# FunctionGenerator.net
KiCad netlist of a schematic drawn in EAGLE
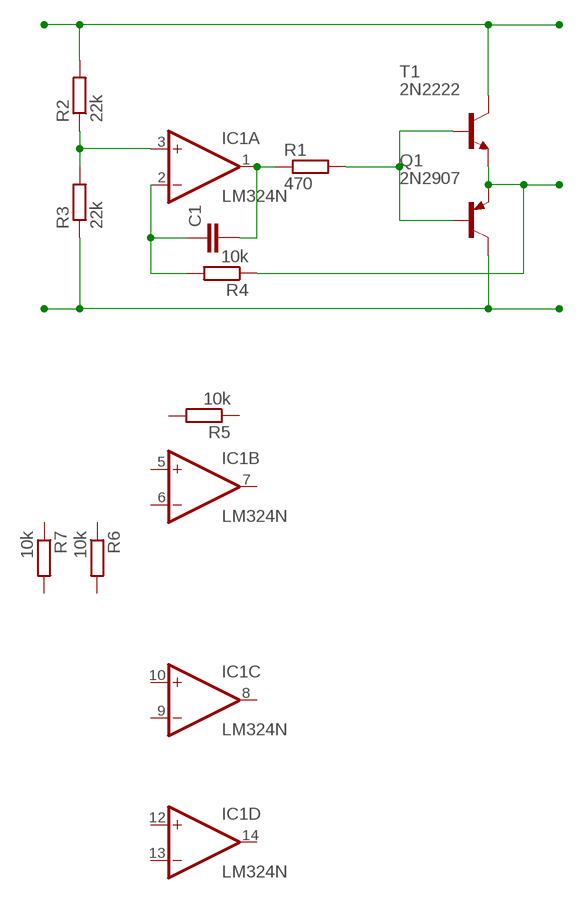
[diagram p0: schematic, sheet 1]

(export (version "E")
  (design (tool "Eeschema 10.0.6"))
  (components
    (comp (ref "C1")
      (value "C-EU050-025X075")
      (footprint "eagle-import:C050-025X075")
      (libsource (lib "eagle-import") (part "C-EU050-025X075"))
    )
    (comp (ref "IC1")
      (value "LM324N")
      (footprint "eagle-import:DIL14")
      (libsource (lib "eagle-import") (part "LM324N"))
    )
    (comp (ref "Q1")
      (value "2N2907")
      (footprint "eagle-import:TO18")
      (libsource (lib "eagle-import") (part "2N2907"))
    )
    (comp (ref "R1")
      (value "470")
      (footprint "eagle-import:0207_10")
      (libsource (lib "eagle-import") (part "R-EU_0207/10"))
    )
    (comp (ref "R2")
      (value "22k")
      (footprint "eagle-import:0207_10")
      (libsource (lib "eagle-import") (part "R-EU_0207/10"))
    )
    (comp (ref "R3")
      (value "22k")
      (footprint "eagle-import:0207_10")
      (libsource (lib "eagle-import") (part "R-EU_0207/10"))
    )
    (comp (ref "R4")
      (value "10k")
      (footprint "eagle-import:0207_10")
      (libsource (lib "eagle-import") (part "R-EU_0207/10"))
    )
    (comp (ref "R5")
      (value "10k")
      (footprint "eagle-import:0207_10")
      (libsource (lib "eagle-import") (part "R-EU_0207/10"))
    )
    (comp (ref "R6")
      (value "10k")
      (footprint "eagle-import:0207_10")
      (libsource (lib "eagle-import") (part "R-EU_0207/10"))
    )
    (comp (ref "R7")
      (value "10k")
      (footprint "eagle-import:0207_10")
      (libsource (lib "eagle-import") (part "R-EU_0207/10"))
    )
    (comp (ref "T1")
      (value "2N2222")
      (footprint "eagle-import:TO18")
      (libsource (lib "eagle-import") (part "2N2222"))
    )
  )
  (nets
    (net (code "1") (name "Net-(IC1A-+IN)") (class "Default")
      (node (ref "IC1") (pin "3") (pinfunction "+IN_3") (pintype "input"))
      (node (ref "R2") (pin "1") (pinfunction "1_1") (pintype "passive"))
      (node (ref "R3") (pin "2") (pinfunction "2_2") (pintype "passive"))
    )
    (net (code "2") (name "Net-(IC1A--IN)") (class "Default")
      (node (ref "C1") (pin "1") (pinfunction "1_1") (pintype "passive"))
      (node (ref "IC1") (pin "2") (pinfunction "-IN_2") (pintype "input"))
      (node (ref "R4") (pin "2") (pinfunction "2_2") (pintype "passive"))
    )
    (net (code "3") (name "Net-(IC1A-OUT)") (class "Default")
      (node (ref "C1") (pin "2") (pinfunction "2_2") (pintype "passive"))
      (node (ref "IC1") (pin "1") (pinfunction "OUT_1") (pintype "output"))
      (node (ref "R1") (pin "1") (pinfunction "1_1") (pintype "passive"))
    )
    (net (code "4") (name "Net-(Q1-B)") (class "Default")
      (node (ref "Q1") (pin "2") (pinfunction "B_2") (pintype "passive"))
      (node (ref "R1") (pin "2") (pinfunction "2_2") (pintype "passive"))
      (node (ref "T1") (pin "2") (pinfunction "B_2") (pintype "passive"))
    )
    (net (code "5") (name "Net-(Q1-C)") (class "Default")
      (node (ref "Q1") (pin "3") (pinfunction "C_3") (pintype "passive"))
      (node (ref "R3") (pin "1") (pinfunction "1_1") (pintype "passive"))
    )
    (net (code "6") (name "Net-(Q1-E)") (class "Default")
      (node (ref "Q1") (pin "1") (pinfunction "E_1") (pintype "passive"))
      (node (ref "R4") (pin "1") (pinfunction "1_1") (pintype "passive"))
      (node (ref "T1") (pin "1") (pinfunction "E_1") (pintype "passive"))
    )
    (net (code "7") (name "Net-(T1-C)") (class "Default")
      (node (ref "R2") (pin "2") (pinfunction "2_2") (pintype "passive"))
      (node (ref "T1") (pin "3") (pinfunction "C_3") (pintype "passive"))
    )
    (net (code "8") (name "unconnected-(IC1B-+IN-Pad5)") (class "Default")
      (node (ref "IC1") (pin "5") (pinfunction "+IN_5") (pintype "input"))
    )
    (net (code "9") (name "unconnected-(IC1B--IN-Pad6)") (class "Default")
      (node (ref "IC1") (pin "6") (pinfunction "-IN_6") (pintype "input"))
    )
    (net (code "10") (name "unconnected-(IC1B-OUT-Pad7)") (class "Default")
      (node (ref "IC1") (pin "7") (pinfunction "OUT_7") (pintype "output"))
    )
    (net (code "11") (name "unconnected-(IC1C-+IN-Pad10)") (class "Default")
      (node (ref "IC1") (pin "10") (pinfunction "+IN_10") (pintype "input"))
    )
    (net (code "12") (name "unconnected-(IC1C--IN-Pad9)") (class "Default")
      (node (ref "IC1") (pin "9") (pinfunction "-IN_9") (pintype "input"))
    )
    (net (code "13") (name "unconnected-(IC1C-OUT-Pad8)") (class "Default")
      (node (ref "IC1") (pin "8") (pinfunction "OUT_8") (pintype "output"))
    )
    (net (code "14") (name "unconnected-(IC1D-+IN-Pad12)") (class "Default")
      (node (ref "IC1") (pin "12") (pinfunction "+IN_12") (pintype "input"))
    )
    (net (code "15") (name "unconnected-(IC1D--IN-Pad13)") (class "Default")
      (node (ref "IC1") (pin "13") (pinfunction "-IN_13") (pintype "input"))
    )
    (net (code "16") (name "unconnected-(IC1D-OUT-Pad14)") (class "Default")
      (node (ref "IC1") (pin "14") (pinfunction "OUT_14") (pintype "output"))
    )
    (net (code "17") (name "unconnected-(R5-Pad1)") (class "Default")
      (node (ref "R5") (pin "1") (pinfunction "1_1") (pintype "passive"))
    )
    (net (code "18") (name "unconnected-(R5-Pad2)") (class "Default")
      (node (ref "R5") (pin "2") (pinfunction "2_2") (pintype "passive"))
    )
    (net (code "19") (name "unconnected-(R6-Pad1)") (class "Default")
      (node (ref "R6") (pin "1") (pinfunction "1_1") (pintype "passive"))
    )
    (net (code "20") (name "unconnected-(R6-Pad2)") (class "Default")
      (node (ref "R6") (pin "2") (pinfunction "2_2") (pintype "passive"))
    )
    (net (code "21") (name "unconnected-(R7-Pad1)") (class "Default")
      (node (ref "R7") (pin "1") (pinfunction "1_1") (pintype "passive"))
    )
    (net (code "22") (name "unconnected-(R7-Pad2)") (class "Default")
      (node (ref "R7") (pin "2") (pinfunction "2_2") (pintype "passive"))
    )
  )
)
